# PAPx2-3.net
KiCad netlist of a schematic drawn in EAGLE
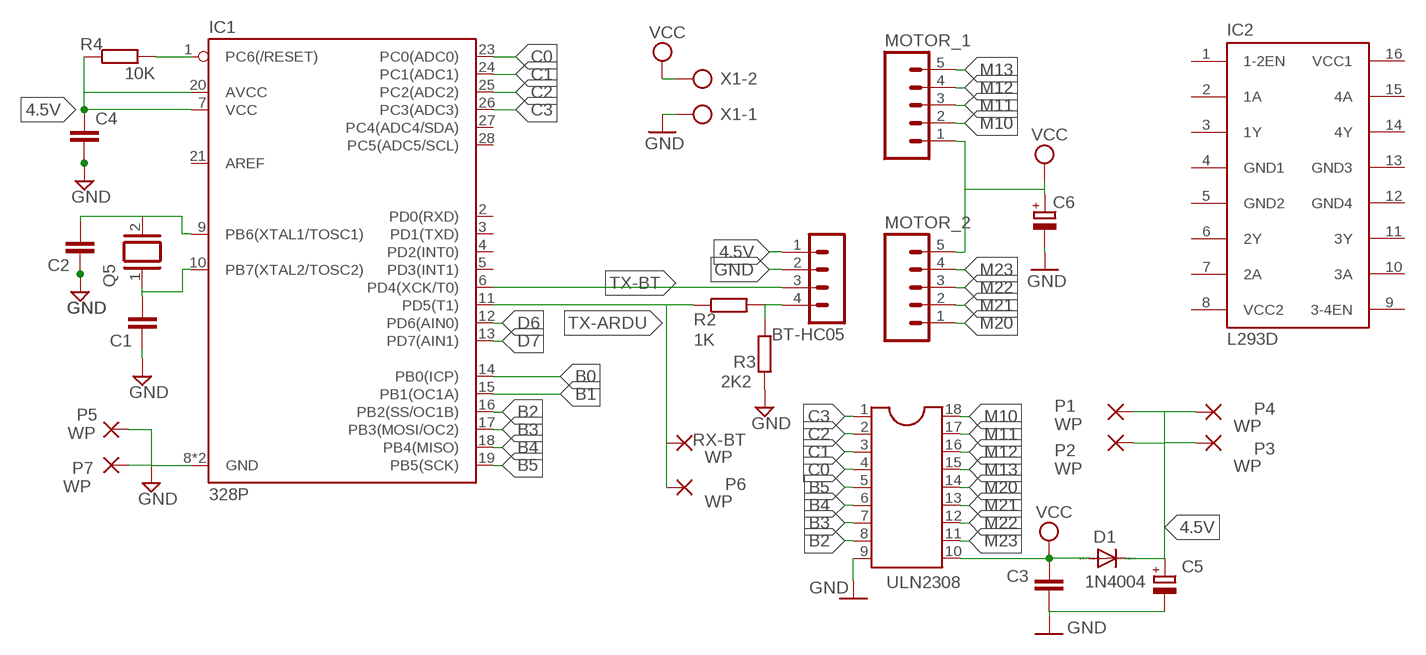
[diagram p0: schematic, sheet 1]

(export (version "E")
  (design (tool "Eeschema 10.0.6"))
  (components
    (comp (ref "BT-HC05")
      (value "MA04-1")
      (footprint "eagle-import:MA04-1")
      (libsource (lib "eagle-import") (part "MA04-1"))
    )
    (comp (ref "C1")
      (value "C-EU025-025X050")
      (footprint "eagle-import:C025-025X050")
      (libsource (lib "eagle-import") (part "C-EU025-025X050"))
    )
    (comp (ref "C2")
      (value "C-EU025-025X050")
      (footprint "eagle-import:C025-025X050")
      (libsource (lib "eagle-import") (part "C-EU025-025X050"))
    )
    (comp (ref "C3")
      (value "C-EU050-025X075")
      (footprint "eagle-import:C050-025X075")
      (libsource (lib "eagle-import") (part "C-EU050-025X075"))
    )
    (comp (ref "C4")
      (value "C-EU050-025X075")
      (footprint "eagle-import:C050-025X075")
      (libsource (lib "eagle-import") (part "C-EU050-025X075"))
    )
    (comp (ref "C5")
      (value "CPOL-EUE2.5-5")
      (footprint "eagle-import:E2,5-5")
      (libsource (lib "eagle-import") (part "CPOL-EUE2.5-5"))
    )
    (comp (ref "C6")
      (value "CPOL-EUE2.5-5")
      (footprint "eagle-import:E2,5-5")
      (libsource (lib "eagle-import") (part "CPOL-EUE2.5-5"))
    )
    (comp (ref "D1")
      (value "1N4004")
      (footprint "eagle-import:DO41-10")
      (libsource (lib "eagle-import") (part "1N4004"))
    )
    (comp (ref "IC1")
      (value "328P")
      (footprint "eagle-import:DIP28")
      (libsource (lib "eagle-import") (part "ATMEGA328P"))
    )
    (comp (ref "IC2")
      (value "L293D")
      (footprint "eagle-import:DIL16")
      (libsource (lib "eagle-import") (part "L293D"))
    )
    (comp (ref "MOTOR_1")
      (value "M05")
      (footprint "eagle-import:05P")
      (libsource (lib "eagle-import") (part "M05"))
    )
    (comp (ref "MOTOR_2")
      (value "M05")
      (footprint "eagle-import:05P")
      (libsource (lib "eagle-import") (part "M05"))
    )
    (comp (ref "P1")
      (value "WP")
      (footprint "eagle-import:1,6_0,8")
      (libsource (lib "eagle-import") (part "WIREPAD1,6/0,8"))
    )
    (comp (ref "P2")
      (value "WP")
      (footprint "eagle-import:1,6_0,8")
      (libsource (lib "eagle-import") (part "WIREPAD1,6/0,8"))
    )
    (comp (ref "P3")
      (value "WP")
      (footprint "eagle-import:1,6_0,8")
      (libsource (lib "eagle-import") (part "WIREPAD1,6/0,8"))
    )
    (comp (ref "P4")
      (value "WP")
      (footprint "eagle-import:1,6_0,8")
      (libsource (lib "eagle-import") (part "WIREPAD1,6/0,8"))
    )
    (comp (ref "P5")
      (value "WP")
      (footprint "eagle-import:1,6_0,8")
      (libsource (lib "eagle-import") (part "WIREPAD1,6/0,8"))
    )
    (comp (ref "P6")
      (value "WP")
      (footprint "eagle-import:1,6_0,8")
      (libsource (lib "eagle-import") (part "WIREPAD1,6/0,8"))
    )
    (comp (ref "P7")
      (value "WP")
      (footprint "eagle-import:1,6_0,8")
      (libsource (lib "eagle-import") (part "WIREPAD1,6/0,8"))
    )
    (comp (ref "Q5")
      (value "XTAL/S")
      (footprint "eagle-import:QS")
      (libsource (lib "eagle-import") (part "XTAL/S"))
    )
    (comp (ref "R2")
      (value "1K")
      (footprint "eagle-import:0204_7")
      (libsource (lib "eagle-import") (part "R-EU_0204/7"))
    )
    (comp (ref "R3")
      (value "2K2")
      (footprint "eagle-import:0204_7")
      (libsource (lib "eagle-import") (part "R-EU_0204/7"))
    )
    (comp (ref "R4")
      (value "10K")
      (footprint "eagle-import:0204_7")
      (libsource (lib "eagle-import") (part "R-EU_0204/7"))
    )
    (comp (ref "RX-BT")
      (value "WP")
      (footprint "eagle-import:1,6_0,8")
      (libsource (lib "eagle-import") (part "WIREPAD1,6/0,8"))
    )
    (comp (ref "ULN2308")
      (value "DIL18")
      (footprint "eagle-import:DIL18")
      (libsource (lib "eagle-import") (part "DIL18"))
    )
    (comp (ref "X1")
      (value "AK500/2")
      (footprint "eagle-import:AK500_2")
      (libsource (lib "eagle-import") (part "AK500/2"))
    )
  )
  (nets
    (net (code "1") (name "/GND1") (class "Default")
      (node (ref "IC2") (pin "4") (pinfunction "GND1_4") (pintype "power_in"))
    )
    (net (code "2") (name "/GND2") (class "Default")
      (node (ref "IC2") (pin "5") (pinfunction "GND2_5") (pintype "power_in"))
    )
    (net (code "3") (name "/GND3") (class "Default")
      (node (ref "IC2") (pin "13") (pinfunction "GND3_13") (pintype "power_in"))
    )
    (net (code "4") (name "/GND4") (class "Default")
      (node (ref "IC2") (pin "12") (pinfunction "GND4_12") (pintype "power_in"))
    )
    (net (code "5") (name "/VCC1") (class "Default")
      (node (ref "IC2") (pin "16") (pinfunction "VCC1_16") (pintype "power_in"))
    )
    (net (code "6") (name "/VCC2") (class "Default")
      (node (ref "IC2") (pin "8") (pinfunction "VCC2_8") (pintype "power_in"))
    )
    (net (code "7") (name "4.5V") (class "Default")
      (node (ref "BT-HC05") (pin "1") (pinfunction "1_1") (pintype "passive"))
      (node (ref "C4") (pin "1") (pinfunction "1_1") (pintype "passive"))
      (node (ref "C5") (pin "+") (pinfunction "+_+") (pintype "passive"))
      (node (ref "D1") (pin "C") (pinfunction "C_C") (pintype "passive"))
      (node (ref "IC1") (pin "20") (pinfunction "AVCC_20") (pintype "bidirectional"))
      (node (ref "IC1") (pin "7") (pinfunction "VCC_7") (pintype "bidirectional"))
      (node (ref "P1") (pin "1") (pinfunction "P_1") (pintype "passive"))
      (node (ref "P2") (pin "1") (pinfunction "P_1") (pintype "passive"))
      (node (ref "P3") (pin "1") (pinfunction "P_1") (pintype "passive"))
      (node (ref "P4") (pin "1") (pinfunction "P_1") (pintype "passive"))
      (node (ref "R4") (pin "1") (pinfunction "1_1") (pintype "passive"))
    )
    (net (code "8") (name "B0") (class "Default")
      (node (ref "IC1") (pin "14") (pinfunction "PB0(ICP)_14") (pintype "bidirectional"))
    )
    (net (code "9") (name "B1") (class "Default")
      (node (ref "IC1") (pin "15") (pinfunction "PB1(OC1A)_15") (pintype "bidirectional"))
    )
    (net (code "10") (name "B2") (class "Default")
      (node (ref "IC1") (pin "16") (pinfunction "PB2(SS/OC1B)_16") (pintype "bidirectional"))
      (node (ref "ULN2308") (pin "8") (pinfunction "8_8") (pintype "passive"))
    )
    (net (code "11") (name "B3") (class "Default")
      (node (ref "IC1") (pin "17") (pinfunction "PB3(MOSI/OC2)_17") (pintype "bidirectional"))
      (node (ref "ULN2308") (pin "7") (pinfunction "7_7") (pintype "passive"))
    )
    (net (code "12") (name "B4") (class "Default")
      (node (ref "IC1") (pin "18") (pinfunction "PB4(MISO)_18") (pintype "bidirectional"))
      (node (ref "ULN2308") (pin "6") (pinfunction "6_6") (pintype "passive"))
    )
    (net (code "13") (name "B5") (class "Default")
      (node (ref "IC1") (pin "19") (pinfunction "PB5(SCK)_19") (pintype "bidirectional"))
      (node (ref "ULN2308") (pin "5") (pinfunction "5_5") (pintype "passive"))
    )
    (net (code "14") (name "C0") (class "Default")
      (node (ref "IC1") (pin "23") (pinfunction "PC0(ADC0)_23") (pintype "bidirectional"))
      (node (ref "ULN2308") (pin "4") (pinfunction "4_4") (pintype "passive"))
    )
    (net (code "15") (name "C1") (class "Default")
      (node (ref "IC1") (pin "24") (pinfunction "PC1(ADC1)_24") (pintype "bidirectional"))
      (node (ref "ULN2308") (pin "3") (pinfunction "3_3") (pintype "passive"))
    )
    (net (code "16") (name "C2") (class "Default")
      (node (ref "IC1") (pin "25") (pinfunction "PC2(ADC2)_25") (pintype "bidirectional"))
      (node (ref "ULN2308") (pin "2") (pinfunction "2_2") (pintype "passive"))
    )
    (net (code "17") (name "C3") (class "Default")
      (node (ref "IC1") (pin "26") (pinfunction "PC3(ADC3)_26") (pintype "bidirectional"))
      (node (ref "ULN2308") (pin "1") (pinfunction "1_1") (pintype "passive"))
    )
    (net (code "18") (name "D6") (class "Default")
      (node (ref "IC1") (pin "12") (pinfunction "PD6(AIN0)_12") (pintype "bidirectional"))
    )
    (net (code "19") (name "D7") (class "Default")
      (node (ref "IC1") (pin "13") (pinfunction "PD7(AIN1)_13") (pintype "bidirectional"))
    )
    (net (code "20") (name "GND") (class "Default")
      (node (ref "BT-HC05") (pin "2") (pinfunction "2_2") (pintype "passive"))
      (node (ref "C1") (pin "1") (pinfunction "1_1") (pintype "passive"))
      (node (ref "C2") (pin "1") (pinfunction "1_1") (pintype "passive"))
      (node (ref "C3") (pin "2") (pinfunction "2_2") (pintype "passive"))
      (node (ref "C4") (pin "2") (pinfunction "2_2") (pintype "passive"))
      (node (ref "C5") (pin "-") (pinfunction "-_-") (pintype "passive"))
      (node (ref "C6") (pin "-") (pinfunction "-_-") (pintype "passive"))
      (node (ref "IC1") (pin "22") (pinfunction "GND_22") (pintype "bidirectional"))
      (node (ref "IC1") (pin "8") (pinfunction "GND_8") (pintype "bidirectional"))
      (node (ref "P5") (pin "1") (pinfunction "P_1") (pintype "passive"))
      (node (ref "P7") (pin "1") (pinfunction "P_1") (pintype "passive"))
      (node (ref "R3") (pin "1") (pinfunction "1_1") (pintype "passive"))
      (node (ref "ULN2308") (pin "9") (pinfunction "9_9") (pintype "passive"))
      (node (ref "X1") (pin "1") (pinfunction "KL_1") (pintype "passive"))
    )
    (net (code "21") (name "M10") (class "Default")
      (node (ref "MOTOR_1") (pin "2") (pinfunction "2_2") (pintype "passive"))
      (node (ref "ULN2308") (pin "18") (pinfunction "18_18") (pintype "passive"))
    )
    (net (code "22") (name "M11") (class "Default")
      (node (ref "MOTOR_1") (pin "3") (pinfunction "3_3") (pintype "passive"))
      (node (ref "ULN2308") (pin "17") (pinfunction "17_17") (pintype "passive"))
    )
    (net (code "23") (name "M12") (class "Default")
      (node (ref "MOTOR_1") (pin "4") (pinfunction "4_4") (pintype "passive"))
      (node (ref "ULN2308") (pin "16") (pinfunction "16_16") (pintype "passive"))
    )
    (net (code "24") (name "M13") (class "Default")
      (node (ref "MOTOR_1") (pin "5") (pinfunction "5_5") (pintype "passive"))
      (node (ref "ULN2308") (pin "15") (pinfunction "15_15") (pintype "passive"))
    )
    (net (code "25") (name "M20") (class "Default")
      (node (ref "MOTOR_2") (pin "1") (pinfunction "1_1") (pintype "passive"))
      (node (ref "ULN2308") (pin "14") (pinfunction "14_14") (pintype "passive"))
    )
    (net (code "26") (name "M21") (class "Default")
      (node (ref "MOTOR_2") (pin "2") (pinfunction "2_2") (pintype "passive"))
      (node (ref "ULN2308") (pin "13") (pinfunction "13_13") (pintype "passive"))
    )
    (net (code "27") (name "M22") (class "Default")
      (node (ref "MOTOR_2") (pin "3") (pinfunction "3_3") (pintype "passive"))
      (node (ref "ULN2308") (pin "12") (pinfunction "12_12") (pintype "passive"))
    )
    (net (code "28") (name "M23") (class "Default")
      (node (ref "MOTOR_2") (pin "4") (pinfunction "4_4") (pintype "passive"))
      (node (ref "ULN2308") (pin "11") (pinfunction "11_11") (pintype "passive"))
    )
    (net (code "29") (name "Net-(BT-HC05-Pad4)") (class "Default")
      (node (ref "BT-HC05") (pin "4") (pinfunction "4_4") (pintype "passive"))
      (node (ref "R2") (pin "2") (pinfunction "2_2") (pintype "passive"))
      (node (ref "R3") (pin "2") (pinfunction "2_2") (pintype "passive"))
    )
    (net (code "30") (name "Net-(IC1-PB6(XTAL1{slash}TOSC1))") (class "Default")
      (node (ref "C2") (pin "2") (pinfunction "2_2") (pintype "passive"))
      (node (ref "IC1") (pin "9") (pinfunction "PB6(XTAL1/TOSC1)_9") (pintype "bidirectional"))
      (node (ref "Q5") (pin "2") (pinfunction "2_2") (pintype "passive"))
    )
    (net (code "31") (name "Net-(IC1-PB7(XTAL2{slash}TOSC2))") (class "Default")
      (node (ref "C1") (pin "2") (pinfunction "2_2") (pintype "passive"))
      (node (ref "IC1") (pin "10") (pinfunction "PB7(XTAL2/TOSC2)_10") (pintype "bidirectional"))
      (node (ref "Q5") (pin "1") (pinfunction "1_1") (pintype "passive"))
    )
    (net (code "32") (name "Net-(IC1-PC6({slash}RESET))") (class "Default")
      (node (ref "IC1") (pin "1") (pinfunction "PC6(/RESET)_1") (pintype "bidirectional"))
      (node (ref "R4") (pin "2") (pinfunction "2_2") (pintype "passive"))
    )
    (net (code "33") (name "TX-ARDU") (class "Default")
      (node (ref "IC1") (pin "11") (pinfunction "PD5(T1)_11") (pintype "bidirectional"))
      (node (ref "P6") (pin "1") (pinfunction "P_1") (pintype "passive"))
      (node (ref "R2") (pin "1") (pinfunction "1_1") (pintype "passive"))
      (node (ref "RX-BT") (pin "1") (pinfunction "P_1") (pintype "passive"))
    )
    (net (code "34") (name "TX-BT") (class "Default")
      (node (ref "BT-HC05") (pin "3") (pinfunction "3_3") (pintype "passive"))
      (node (ref "IC1") (pin "6") (pinfunction "PD4(XCK/T0)_6") (pintype "bidirectional"))
    )
    (net (code "35") (name "VCC") (class "Default")
      (node (ref "C3") (pin "1") (pinfunction "1_1") (pintype "passive"))
      (node (ref "C6") (pin "+") (pinfunction "+_+") (pintype "passive"))
      (node (ref "D1") (pin "A") (pinfunction "A_A") (pintype "passive"))
      (node (ref "MOTOR_1") (pin "1") (pinfunction "1_1") (pintype "passive"))
      (node (ref "MOTOR_2") (pin "5") (pinfunction "5_5") (pintype "passive"))
      (node (ref "ULN2308") (pin "10") (pinfunction "10_10") (pintype "passive"))
      (node (ref "X1") (pin "2") (pinfunction "KL_2") (pintype "passive"))
    )
    (net (code "36") (name "unconnected-(IC1-AREF-Pad21)") (class "Default")
      (node (ref "IC1") (pin "21") (pinfunction "AREF_21") (pintype "bidirectional"))
    )
    (net (code "37") (name "unconnected-(IC1-PC4(ADC4{slash}SDA)-Pad27)") (class "Default")
      (node (ref "IC1") (pin "27") (pinfunction "PC4(ADC4/SDA)_27") (pintype "bidirectional"))
    )
    (net (code "38") (name "unconnected-(IC1-PC5(ADC5{slash}SCL)-Pad28)") (class "Default")
      (node (ref "IC1") (pin "28") (pinfunction "PC5(ADC5/SCL)_28") (pintype "bidirectional"))
    )
    (net (code "39") (name "unconnected-(IC1-PD0(RXD)-Pad2)") (class "Default")
      (node (ref "IC1") (pin "2") (pinfunction "PD0(RXD)_2") (pintype "bidirectional"))
    )
    (net (code "40") (name "unconnected-(IC1-PD1(TXD)-Pad3)") (class "Default")
      (node (ref "IC1") (pin "3") (pinfunction "PD1(TXD)_3") (pintype "bidirectional"))
    )
    (net (code "41") (name "unconnected-(IC1-PD2(INT0)-Pad4)") (class "Default")
      (node (ref "IC1") (pin "4") (pinfunction "PD2(INT0)_4") (pintype "bidirectional"))
    )
    (net (code "42") (name "unconnected-(IC1-PD3(INT1)-Pad5)") (class "Default")
      (node (ref "IC1") (pin "5") (pinfunction "PD3(INT1)_5") (pintype "bidirectional"))
    )
    (net (code "43") (name "unconnected-(IC2-1-2EN-Pad1)") (class "Default")
      (node (ref "IC2") (pin "1") (pinfunction "1-2EN_1") (pintype "input"))
    )
    (net (code "44") (name "unconnected-(IC2-1A-Pad2)") (class "Default")
      (node (ref "IC2") (pin "2") (pinfunction "1A_2") (pintype "input"))
    )
    (net (code "45") (name "unconnected-(IC2-1Y-Pad3)") (class "Default")
      (node (ref "IC2") (pin "3") (pinfunction "1Y_3") (pintype "output"))
    )
    (net (code "46") (name "unconnected-(IC2-2A-Pad7)") (class "Default")
      (node (ref "IC2") (pin "7") (pinfunction "2A_7") (pintype "input"))
    )
    (net (code "47") (name "unconnected-(IC2-2Y-Pad6)") (class "Default")
      (node (ref "IC2") (pin "6") (pinfunction "2Y_6") (pintype "output"))
    )
    (net (code "48") (name "unconnected-(IC2-3-4EN-Pad9)") (class "Default")
      (node (ref "IC2") (pin "9") (pinfunction "3-4EN_9") (pintype "input"))
    )
    (net (code "49") (name "unconnected-(IC2-3A-Pad10)") (class "Default")
      (node (ref "IC2") (pin "10") (pinfunction "3A_10") (pintype "input"))
    )
    (net (code "50") (name "unconnected-(IC2-3Y-Pad11)") (class "Default")
      (node (ref "IC2") (pin "11") (pinfunction "3Y_11") (pintype "output"))
    )
    (net (code "51") (name "unconnected-(IC2-4A-Pad15)") (class "Default")
      (node (ref "IC2") (pin "15") (pinfunction "4A_15") (pintype "input"))
    )
    (net (code "52") (name "unconnected-(IC2-4Y-Pad14)") (class "Default")
      (node (ref "IC2") (pin "14") (pinfunction "4Y_14") (pintype "output"))
    )
  )
)
